# 8266HomeKitSwitch.net
KiCad netlist of a schematic drawn in Altium Designer
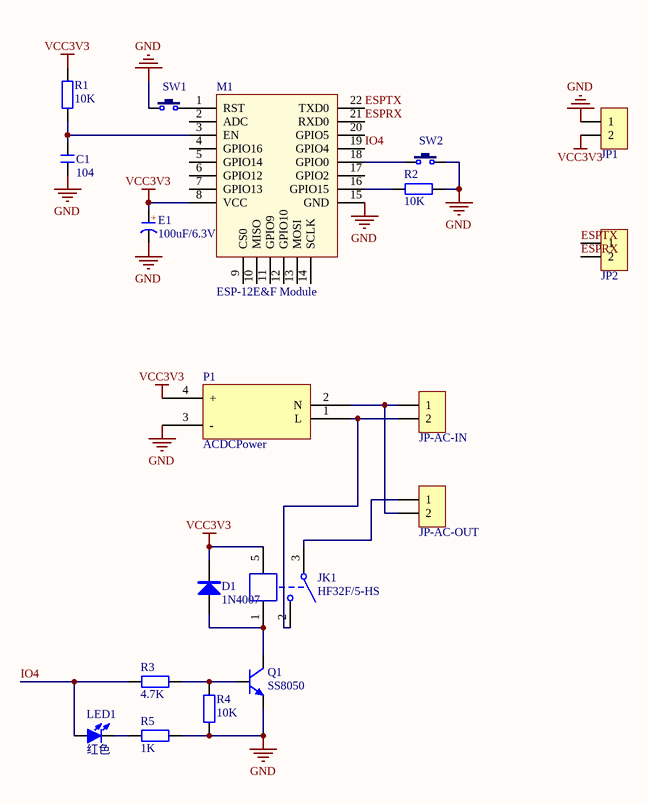
[diagram p0: 8266HomeKitSwitch.SchDoc]

(export (version "E")
  (design (tool "Eeschema 10.0.6"))
  (components
    (comp (ref "C1")
      (value "104")
      (footprint "C 0603_L")
      (description "无极性贴片电容")
      (fields (field (name "版权归属") "源创客"))
      (libsource (lib "3.1   - 电阻-电容-电感") (part "C"))
    )
    (comp (ref "D1")
      (value "1N4007")
      (footprint "SOD-123")
      (description "整流二极管")
      (fields (field (name "版权归属") "源创客"))
      (libsource (lib "8.1   - 二极管-整流桥") (part "1N4007"))
    )
    (comp (ref "E1")
      (value "100uF/6.3V")
      (footprint "CD A(3216)")
      (description "贴片钽电容")
      (fields (field (name "版权归属") "源创客"))
      (libsource (lib "3.1   - 电阻-电容-电感") (part "C-CD"))
    )
    (comp (ref "JK1")
      (value "HF32F/5-HS")
      (footprint "JZC-32F_1H")
      (description "5V一组常开")
      (fields (field (name "版权归属") "源创客"))
      (libsource (lib "7.1   - 继电器") (part "HF32F/5-HS"))
    )
    (comp (ref "JP-AC-IN")
      (value "HDR-1X2")
      (footprint "KF128-3.81-2P")
      (description "2P接插件")
      (fields (field (name "版权归属") "源创客"))
      (libsource (lib "4.8   - 接插件-脚距3.81") (part "Header 2"))
    )
    (comp (ref "JP-AC-OUT")
      (value "HDR-1X2")
      (footprint "KF128-3.81-2P")
      (description "2P接插件")
      (fields (field (name "版权归属") "源创客"))
      (libsource (lib "4.8   - 接插件-脚距3.81") (part "Header 2"))
    )
    (comp (ref "JP1")
      (value "HDR-1X2")
      (footprint "HDR2.54-LI-2P")
      (description "2P接插件")
      (fields (field (name "版权归属") "源创客"))
      (libsource (lib "4.6   - 接插件-脚距2.54") (part "Header 2"))
    )
    (comp (ref "JP2")
      (value "HDR-1X2")
      (footprint "HDR2.54-LI-2P")
      (description "2P接插件")
      (fields (field (name "版权归属") "源创客"))
      (libsource (lib "4.6   - 接插件-脚距2.54") (part "Header 2"))
    )
    (comp (ref "LED1")
      (value "红色")
      (footprint "LED 0603B")
      (description "贴片LED")
      (fields (field (name "版权归属") "源创客"))
      (libsource (lib "9.1   - LED") (part "LED-SMD"))
    )
    (comp (ref "M1")
      (value "ESP-12E&F Module")
      (footprint "ESP-12E&F Module")
      (libsource (lib "MyLib") (part "ESP-12E&F Module"))
    )
    (comp (ref "P1") (value "ACDCPower") (footprint "ADDC") (libsource (lib "MyLib") (part "ACDCPower")))
    (comp (ref "Q1")
      (value "SS8050")
      (footprint "SOT23-3N")
      (description "高频放大-NPN型")
      (fields (field (name "版权归属") "源创客"))
      (libsource (lib "6.2   - 三极管") (part "8050-SMD"))
    )
    (comp (ref "R1")
      (value "10K")
      (footprint "R 0603_L")
      (description "贴片电阻")
      (fields (field (name "版权归属") "源创客"))
      (libsource (lib "3.1   - 电阻-电容-电感") (part "R"))
    )
    (comp (ref "R2")
      (value "10K")
      (footprint "R 0603_L")
      (description "贴片电阻")
      (fields (field (name "版权归属") "源创客"))
      (libsource (lib "3.1   - 电阻-电容-电感") (part "R"))
    )
    (comp (ref "R3")
      (value "4.7K")
      (footprint "R 0603_L")
      (description "贴片电阻")
      (fields (field (name "版权归属") "源创客"))
      (libsource (lib "3.1   - 电阻-电容-电感") (part "R"))
    )
    (comp (ref "R4")
      (value "10K")
      (footprint "R 0603_L")
      (description "贴片电阻")
      (fields (field (name "版权归属") "源创客"))
      (libsource (lib "3.1   - 电阻-电容-电感") (part "R"))
    )
    (comp (ref "R5")
      (value "1K")
      (footprint "R 0603_L")
      (description "贴片电阻")
      (fields (field (name "版权归属") "源创客"))
      (libsource (lib "3.1   - 电阻-电容-电感") (part "R"))
    )
    (comp (ref "SW1")
      (value "3x4x5")
      (footprint "TS3x4x2")
      (description "3x4轻触开关")
      (fields (field (name "版权归属") "源创客"))
      (libsource (lib "5.1   - 按键-开关") (part "TS 3x4"))
    )
    (comp (ref "SW2")
      (value "3x4x5")
      (footprint "TS3x4x2")
      (description "3x4轻触开关")
      (fields (field (name "版权归属") "源创客"))
      (libsource (lib "5.1   - 按键-开关") (part "TS 3x4"))
    )
  )
  (nets
    (net (code "1") (name "/ESPRX") (class "Default")
      (node (ref "JP2") (pin "2") (pinfunction "2_2") (pintype "passive"))
      (node (ref "M1") (pin "21") (pinfunction "RXD0_21") (pintype "passive"))
    )
    (net (code "2") (name "/ESPTX") (class "Default")
      (node (ref "JP2") (pin "1") (pinfunction "1_1") (pintype "passive"))
      (node (ref "M1") (pin "22") (pinfunction "TXD0_22") (pintype "passive"))
    )
    (net (code "3") (name "/IO4") (class "Default")
      (node (ref "LED1") (pin "1") (pinfunction "A_1") (pintype "passive"))
      (node (ref "M1") (pin "19") (pinfunction "GPIO4_19") (pintype "passive"))
      (node (ref "R3") (pin "2") (pinfunction "2_2") (pintype "passive"))
    )
    (net (code "4") (name "GND") (class "Default")
      (node (ref "C1") (pin "1") (pinfunction "1_1") (pintype "passive"))
      (node (ref "E1") (pin "2") (pinfunction "K_2") (pintype "passive"))
      (node (ref "JP1") (pin "1") (pinfunction "1_1") (pintype "passive"))
      (node (ref "M1") (pin "15") (pinfunction "GND_15") (pintype "passive"))
      (node (ref "P1") (pin "3") (pinfunction "-_3") (pintype "passive"))
      (node (ref "Q1") (pin "2") (pinfunction "E_2") (pintype "passive"))
      (node (ref "R2") (pin "1") (pinfunction "1_1") (pintype "passive"))
      (node (ref "R4") (pin "2") (pinfunction "2_2") (pintype "passive"))
      (node (ref "R5") (pin "1") (pinfunction "1_1") (pintype "passive"))
      (node (ref "SW1") (pin "1") (pinfunction "1_1") (pintype "passive"))
      (node (ref "SW2") (pin "2") (pinfunction "2_2") (pintype "passive"))
    )
    (net (code "5") (name "Net-(D1-A)") (class "Default")
      (node (ref "D1") (pin "1") (pinfunction "A_1") (pintype "passive"))
      (node (ref "JK1") (pin "1") (pinfunction "1_1") (pintype "passive"))
      (node (ref "Q1") (pin "3") (pinfunction "C_3") (pintype "passive"))
    )
    (net (code "6") (name "Net-(JK1-Pad3)") (class "Default")
      (node (ref "JK1") (pin "3") (pinfunction "3_3") (pintype "passive"))
      (node (ref "JP-AC-OUT") (pin "1") (pinfunction "1_1") (pintype "passive"))
    )
    (net (code "7") (name "Net-(LED1-K)") (class "Default")
      (node (ref "LED1") (pin "2") (pinfunction "K_2") (pintype "passive"))
      (node (ref "R5") (pin "2") (pinfunction "2_2") (pintype "passive"))
    )
    (net (code "8") (name "Net-(M1-EN)") (class "Default")
      (node (ref "C1") (pin "2") (pinfunction "2_2") (pintype "passive"))
      (node (ref "M1") (pin "3") (pinfunction "EN_3") (pintype "passive"))
      (node (ref "R1") (pin "1") (pinfunction "1_1") (pintype "passive"))
    )
    (net (code "9") (name "Net-(M1-GPIO0)") (class "Default")
      (node (ref "M1") (pin "18") (pinfunction "GPIO0_18") (pintype "passive"))
      (node (ref "SW2") (pin "1") (pinfunction "1_1") (pintype "passive"))
    )
    (net (code "10") (name "Net-(M1-GPIO15)") (class "Default")
      (node (ref "M1") (pin "16") (pinfunction "GPIO15_16") (pintype "passive"))
      (node (ref "R2") (pin "2") (pinfunction "2_2") (pintype "passive"))
    )
    (net (code "11") (name "Net-(M1-RST)") (class "Default")
      (node (ref "M1") (pin "1") (pinfunction "RST_1") (pintype "passive"))
      (node (ref "SW1") (pin "2") (pinfunction "2_2") (pintype "passive"))
    )
    (net (code "12") (name "Net-(P1-L)") (class "Default")
      (node (ref "JK1") (pin "2") (pinfunction "2_2") (pintype "passive"))
      (node (ref "JP-AC-IN") (pin "2") (pinfunction "2_2") (pintype "passive"))
      (node (ref "P1") (pin "1") (pinfunction "L_1") (pintype "passive"))
    )
    (net (code "13") (name "Net-(P1-N)") (class "Default")
      (node (ref "JP-AC-IN") (pin "1") (pinfunction "1_1") (pintype "passive"))
      (node (ref "JP-AC-OUT") (pin "2") (pinfunction "2_2") (pintype "passive"))
      (node (ref "P1") (pin "2") (pinfunction "N_2") (pintype "passive"))
    )
    (net (code "14") (name "Net-(Q1-B)") (class "Default")
      (node (ref "Q1") (pin "1") (pinfunction "B_1") (pintype "passive"))
      (node (ref "R3") (pin "1") (pinfunction "1_1") (pintype "passive"))
      (node (ref "R4") (pin "1") (pinfunction "1_1") (pintype "passive"))
    )
    (net (code "15") (name "VCC3V3") (class "Default")
      (node (ref "D1") (pin "2") (pinfunction "K_2") (pintype "passive"))
      (node (ref "E1") (pin "1") (pinfunction "A_1") (pintype "passive"))
      (node (ref "JK1") (pin "5") (pinfunction "5_5") (pintype "passive"))
      (node (ref "JP1") (pin "2") (pinfunction "2_2") (pintype "passive"))
      (node (ref "M1") (pin "8") (pinfunction "VCC_8") (pintype "passive"))
      (node (ref "P1") (pin "4") (pinfunction "+_4") (pintype "passive"))
      (node (ref "R1") (pin "2") (pinfunction "2_2") (pintype "passive"))
    )
    (net (code "16") (name "unconnected-(M1-ADC-Pad2)") (class "Default")
      (node (ref "M1") (pin "2") (pinfunction "ADC_2") (pintype "passive"))
    )
    (net (code "17") (name "unconnected-(M1-CS0-Pad9)") (class "Default")
      (node (ref "M1") (pin "9") (pinfunction "CS0_9") (pintype "passive"))
    )
    (net (code "18") (name "unconnected-(M1-GPIO2-Pad17)") (class "Default")
      (node (ref "M1") (pin "17") (pinfunction "GPIO2_17") (pintype "passive"))
    )
    (net (code "19") (name "unconnected-(M1-GPIO5-Pad20)") (class "Default")
      (node (ref "M1") (pin "20") (pinfunction "GPIO5_20") (pintype "passive"))
    )
    (net (code "20") (name "unconnected-(M1-GPIO9-Pad11)") (class "Default")
      (node (ref "M1") (pin "11") (pinfunction "GPIO9_11") (pintype "passive"))
    )
    (net (code "21") (name "unconnected-(M1-GPIO10-Pad12)") (class "Default")
      (node (ref "M1") (pin "12") (pinfunction "GPIO10_12") (pintype "passive"))
    )
    (net (code "22") (name "unconnected-(M1-GPIO12-Pad6)") (class "Default")
      (node (ref "M1") (pin "6") (pinfunction "GPIO12_6") (pintype "passive"))
    )
    (net (code "23") (name "unconnected-(M1-GPIO13-Pad7)") (class "Default")
      (node (ref "M1") (pin "7") (pinfunction "GPIO13_7") (pintype "passive"))
    )
    (net (code "24") (name "unconnected-(M1-GPIO14-Pad5)") (class "Default")
      (node (ref "M1") (pin "5") (pinfunction "GPIO14_5") (pintype "passive"))
    )
    (net (code "25") (name "unconnected-(M1-GPIO16-Pad4)") (class "Default")
      (node (ref "M1") (pin "4") (pinfunction "GPIO16_4") (pintype "passive"))
    )
    (net (code "26") (name "unconnected-(M1-MISO-Pad10)") (class "Default")
      (node (ref "M1") (pin "10") (pinfunction "MISO_10") (pintype "passive"))
    )
    (net (code "27") (name "unconnected-(M1-MOSI-Pad13)") (class "Default")
      (node (ref "M1") (pin "13") (pinfunction "MOSI_13") (pintype "passive"))
    )
    (net (code "28") (name "unconnected-(M1-SCLK-Pad14)") (class "Default")
      (node (ref "M1") (pin "14") (pinfunction "SCLK_14") (pintype "passive"))
    )
  )
)
